# nRF24L01_RFX2401_noBalun_SMD_0603.net
KiCad netlist of a schematic drawn in EAGLE
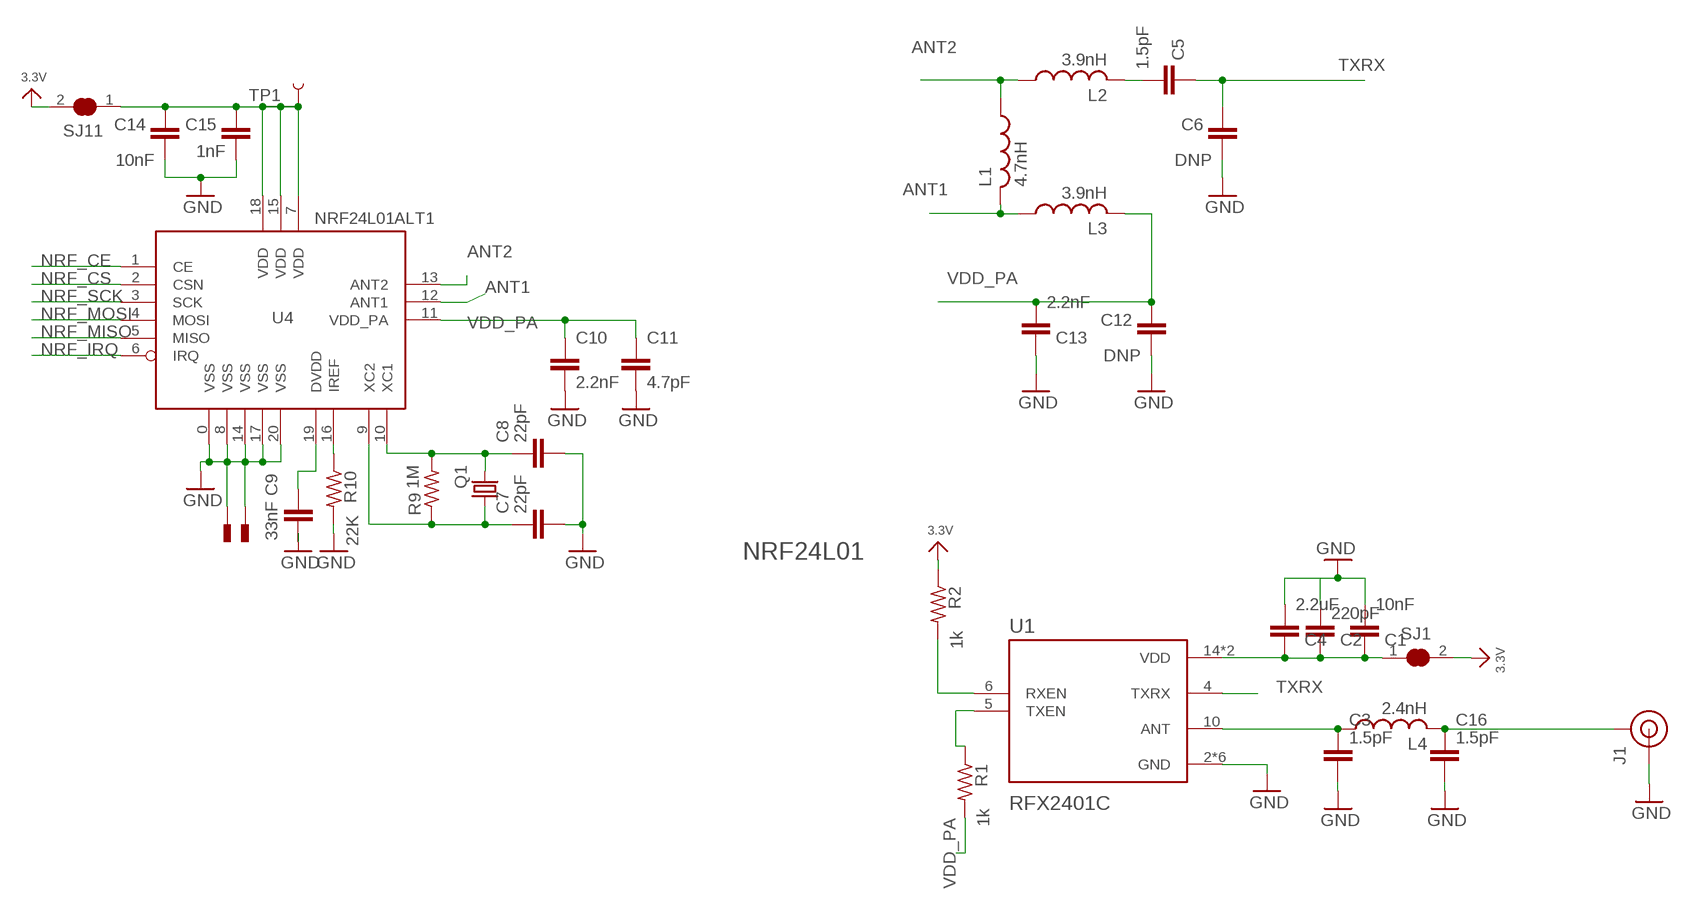
[diagram p0: schematic, sheet 1]

(export (version "E")
  (design (tool "Eeschema 10.0.6"))
  (components
    (comp (ref "C1")
      (value "10nF")
      (footprint "eagle-import:C0603")
      (libsource (lib "eagle-import") (part "C-EUC0603"))
    )
    (comp (ref "C2")
      (value "220pF")
      (footprint "eagle-import:C0603")
      (libsource (lib "eagle-import") (part "C-EUC0603"))
    )
    (comp (ref "C3")
      (value "1.5pF")
      (footprint "eagle-import:C0603")
      (libsource (lib "eagle-import") (part "C-EUC0603"))
    )
    (comp (ref "C4")
      (value "2.2uF")
      (footprint "eagle-import:C0603")
      (libsource (lib "eagle-import") (part "C-EUC0603"))
    )
    (comp (ref "C5")
      (value "1.5pF")
      (footprint "eagle-import:C0603")
      (libsource (lib "eagle-import") (part "C-EUC0603"))
    )
    (comp (ref "C6")
      (value "DNP")
      (footprint "eagle-import:C0603")
      (libsource (lib "eagle-import") (part "C-EUC0603"))
    )
    (comp (ref "C7")
      (value "22pF")
      (footprint "eagle-import:C0603")
      (libsource (lib "eagle-import") (part "C-EUC0603"))
    )
    (comp (ref "C8")
      (value "22pF")
      (footprint "eagle-import:C0603")
      (libsource (lib "eagle-import") (part "C-EUC0603"))
    )
    (comp (ref "C9")
      (value "33nF")
      (footprint "eagle-import:C0603")
      (libsource (lib "eagle-import") (part "C-EUC0603"))
    )
    (comp (ref "C10")
      (value "2.2nF")
      (footprint "eagle-import:C0603")
      (libsource (lib "eagle-import") (part "C-EUC0603"))
    )
    (comp (ref "C11")
      (value "4.7pF")
      (footprint "eagle-import:C0603")
      (libsource (lib "eagle-import") (part "C-EUC0603"))
    )
    (comp (ref "C12")
      (value "DNP")
      (footprint "eagle-import:C0603")
      (libsource (lib "eagle-import") (part "C-EUC0603"))
    )
    (comp (ref "C13")
      (value "2.2nF")
      (footprint "eagle-import:C0603")
      (libsource (lib "eagle-import") (part "C-EUC0603"))
    )
    (comp (ref "C14")
      (value "10nF")
      (footprint "eagle-import:C0603")
      (libsource (lib "eagle-import") (part "C-EUC0603"))
    )
    (comp (ref "C15")
      (value "1nF")
      (footprint "eagle-import:C0603")
      (libsource (lib "eagle-import") (part "C-EUC0603"))
    )
    (comp (ref "C16")
      (value "1.5pF")
      (footprint "eagle-import:C0603")
      (libsource (lib "eagle-import") (part "C-EUC0603"))
    )
    (comp (ref "J1")
      (value "U.FL")
      (footprint "eagle-import:U.FL")
      (libsource (lib "eagle-import") (part "U.FL2PIN"))
    )
    (comp (ref "L1")
      (value "4.7nH")
      (footprint "eagle-import:L0603")
      (libsource (lib "eagle-import") (part "L-USL0603"))
    )
    (comp (ref "L2")
      (value "3.9nH")
      (footprint "eagle-import:L0603")
      (libsource (lib "eagle-import") (part "L-USL0603"))
    )
    (comp (ref "L3")
      (value "3.9nH")
      (footprint "eagle-import:L0603")
      (libsource (lib "eagle-import") (part "L-USL0603"))
    )
    (comp (ref "L4")
      (value "2.4nH")
      (footprint "eagle-import:L0603")
      (libsource (lib "eagle-import") (part "L-USL0603"))
    )
    (comp (ref "Q1")
      (value "KX-7")
      (footprint "eagle-import:3.2X2.5_KX-7")
      (libsource (lib "eagle-import") (part "KX-7"))
    )
    (comp (ref "R1")
      (value "1k")
      (footprint "eagle-import:R0603")
      (libsource (lib "eagle-import") (part "R-US_R0603"))
    )
    (comp (ref "R2")
      (value "1k")
      (footprint "eagle-import:R0603")
      (libsource (lib "eagle-import") (part "R-US_R0603"))
    )
    (comp (ref "R9")
      (value "1M")
      (footprint "eagle-import:R0603")
      (libsource (lib "eagle-import") (part "R-US_R0603"))
    )
    (comp (ref "R10")
      (value "22K")
      (footprint "eagle-import:R0603")
      (libsource (lib "eagle-import") (part "R-US_R0603"))
    )
    (comp (ref "SJ1")
      (value "SOLDERJUMPER_CLOSED")
      (footprint "eagle-import:SOLDERJUMPER_CLOSEDWIRE")
      (libsource (lib "eagle-import") (part "SOLDERJUMPER_CLOSED"))
    )
    (comp (ref "SJ11")
      (value "SOLDERJUMPER_CLOSED")
      (footprint "eagle-import:SOLDERJUMPER_CLOSEDWIRE")
      (libsource (lib "eagle-import") (part "SOLDERJUMPER_CLOSED"))
    )
    (comp (ref "TP1")
      (value "TEST-POINT3X5")
      (footprint "eagle-import:PAD.03X.05")
      (libsource (lib "eagle-import") (part "TEST-POINT3X5"))
    )
    (comp (ref "U$27")
      (value "PAD")
      (footprint "eagle-import:PAD-0.008")
      (libsource (lib "eagle-import") (part "PAD"))
    )
    (comp (ref "U$28")
      (value "PAD")
      (footprint "eagle-import:PAD-0.008")
      (libsource (lib "eagle-import") (part "PAD"))
    )
    (comp (ref "U1")
      (value "RFX2401C")
      (footprint "eagle-import:QFN50P300X300X60-17N")
      (fields (field (name "MF") "Skyworks Solutions"))
      (libsource (lib "eagle-import") (part "RFX2401C"))
    )
    (comp (ref "U4")
      (value "NRF24L01ALT1")
      (footprint "eagle-import:QFN20_ALT1")
      (libsource (lib "eagle-import") (part "NRF24L01ALT1"))
    )
  )
  (nets
    (net (code "1") (name "/ANT1") (class "Default")
      (node (ref "L1") (pin "2") (pinfunction "2_2") (pintype "passive"))
      (node (ref "L3") (pin "1") (pinfunction "1_1") (pintype "passive"))
      (node (ref "U4") (pin "12") (pinfunction "ANT1_12") (pintype "output"))
    )
    (net (code "2") (name "/ANT2") (class "Default")
      (node (ref "L1") (pin "1") (pinfunction "1_1") (pintype "passive"))
      (node (ref "L2") (pin "1") (pinfunction "1_1") (pintype "passive"))
      (node (ref "U4") (pin "13") (pinfunction "ANT2_13") (pintype "output"))
    )
    (net (code "3") (name "/NRF_CE") (class "Default")
      (node (ref "U4") (pin "1") (pinfunction "CE_1") (pintype "input"))
    )
    (net (code "4") (name "/NRF_CS") (class "Default")
      (node (ref "U4") (pin "2") (pinfunction "CSN_2") (pintype "input"))
    )
    (net (code "5") (name "/NRF_IRQ") (class "Default")
      (node (ref "U4") (pin "6") (pinfunction "IRQ_6") (pintype "output"))
    )
    (net (code "6") (name "/NRF_MISO") (class "Default")
      (node (ref "U4") (pin "5") (pinfunction "MISO_5") (pintype "output"))
    )
    (net (code "7") (name "/NRF_MOSI") (class "Default")
      (node (ref "U4") (pin "4") (pinfunction "MOSI_4") (pintype "input"))
    )
    (net (code "8") (name "/NRF_SCK") (class "Default")
      (node (ref "U4") (pin "3") (pinfunction "SCK_3") (pintype "input"))
    )
    (net (code "9") (name "/TXRX") (class "Default")
      (node (ref "C5") (pin "2") (pinfunction "2_2") (pintype "passive"))
      (node (ref "C6") (pin "2") (pinfunction "2_2") (pintype "passive"))
      (node (ref "U1") (pin "4") (pinfunction "TXRX_4") (pintype "bidirectional"))
    )
    (net (code "10") (name "/VDD_PA") (class "Default")
      (node (ref "C10") (pin "1") (pinfunction "1_1") (pintype "passive"))
      (node (ref "C11") (pin "1") (pinfunction "1_1") (pintype "passive"))
      (node (ref "C12") (pin "2") (pinfunction "2_2") (pintype "passive"))
      (node (ref "C13") (pin "1") (pinfunction "1_1") (pintype "passive"))
      (node (ref "L3") (pin "2") (pinfunction "2_2") (pintype "passive"))
      (node (ref "R1") (pin "2") (pinfunction "2_2") (pintype "passive"))
      (node (ref "U4") (pin "11") (pinfunction "VDD_PA_11") (pintype "power_in"))
    )
    (net (code "11") (name "3.3V") (class "Default")
      (node (ref "R2") (pin "1") (pinfunction "1_1") (pintype "passive"))
      (node (ref "SJ1") (pin "2") (pinfunction "2_2") (pintype "passive"))
      (node (ref "SJ11") (pin "2") (pinfunction "2_2") (pintype "passive"))
    )
    (net (code "12") (name "GND") (class "Default")
      (node (ref "C1") (pin "1") (pinfunction "1_1") (pintype "passive"))
      (node (ref "C10") (pin "2") (pinfunction "2_2") (pintype "passive"))
      (node (ref "C11") (pin "2") (pinfunction "2_2") (pintype "passive"))
      (node (ref "C12") (pin "1") (pinfunction "1_1") (pintype "passive"))
      (node (ref "C13") (pin "2") (pinfunction "2_2") (pintype "passive"))
      (node (ref "C14") (pin "1") (pinfunction "1_1") (pintype "passive"))
      (node (ref "C15") (pin "1") (pinfunction "1_1") (pintype "passive"))
      (node (ref "C16") (pin "2") (pinfunction "2_2") (pintype "passive"))
      (node (ref "C2") (pin "1") (pinfunction "1_1") (pintype "passive"))
      (node (ref "C3") (pin "2") (pinfunction "2_2") (pintype "passive"))
      (node (ref "C4") (pin "1") (pinfunction "1_1") (pintype "passive"))
      (node (ref "C6") (pin "1") (pinfunction "1_1") (pintype "passive"))
      (node (ref "C7") (pin "2") (pinfunction "2_2") (pintype "passive"))
      (node (ref "C8") (pin "2") (pinfunction "2_2") (pintype "passive"))
      (node (ref "C9") (pin "2") (pinfunction "2_2") (pintype "passive"))
      (node (ref "J1") (pin "FEED") (pinfunction "SIGNAL_FEED") (pintype "bidirectional"))
      (node (ref "R10") (pin "2") (pinfunction "2_2") (pintype "passive"))
      (node (ref "U$27") (pin "P$1") (pinfunction "P$1_P$1") (pintype "bidirectional"))
      (node (ref "U$28") (pin "P$1") (pinfunction "P$1_P$1") (pintype "bidirectional"))
      (node (ref "U1") (pin "11") (pinfunction "GND_11") (pintype "power_in"))
      (node (ref "U1") (pin "17") (pinfunction "GND_17") (pintype "power_in"))
      (node (ref "U1") (pin "2") (pinfunction "GND_2") (pintype "power_in"))
      (node (ref "U1") (pin "3") (pinfunction "GND_3") (pintype "power_in"))
      (node (ref "U1") (pin "8") (pinfunction "GND_8") (pintype "power_in"))
      (node (ref "U1") (pin "9") (pinfunction "GND_9") (pintype "power_in"))
      (node (ref "U4") (pin "0") (pinfunction "VSS_0") (pintype "power_in"))
      (node (ref "U4") (pin "14") (pinfunction "VSS_14") (pintype "power_in"))
      (node (ref "U4") (pin "17") (pinfunction "VSS_17") (pintype "power_in"))
      (node (ref "U4") (pin "20") (pinfunction "VSS_20") (pintype "power_in"))
      (node (ref "U4") (pin "8") (pinfunction "VSS_8") (pintype "power_in"))
    )
    (net (code "13") (name "Net-(C1-Pad2)") (class "Default")
      (node (ref "C1") (pin "2") (pinfunction "2_2") (pintype "passive"))
      (node (ref "C2") (pin "2") (pinfunction "2_2") (pintype "passive"))
      (node (ref "C4") (pin "2") (pinfunction "2_2") (pintype "passive"))
      (node (ref "SJ1") (pin "1") (pinfunction "1_1") (pintype "passive"))
      (node (ref "U1") (pin "14") (pinfunction "VDD_14") (pintype "power_in"))
      (node (ref "U1") (pin "16") (pinfunction "VDD_16") (pintype "power_in"))
    )
    (net (code "14") (name "Net-(C5-Pad1)") (class "Default")
      (node (ref "C5") (pin "1") (pinfunction "1_1") (pintype "passive"))
      (node (ref "L2") (pin "2") (pinfunction "2_2") (pintype "passive"))
    )
    (net (code "15") (name "Net-(C16-Pad1)") (class "Default")
      (node (ref "C16") (pin "1") (pinfunction "1_1") (pintype "passive"))
      (node (ref "J1") (pin "1") (pinfunction "GND_1") (pintype "bidirectional"))
      (node (ref "J1") (pin "2") (pinfunction "GND_2") (pintype "bidirectional"))
      (node (ref "L4") (pin "2") (pinfunction "2_2") (pintype "passive"))
    )
    (net (code "16") (name "Net-(Q1-2)") (class "Default")
      (node (ref "C8") (pin "1") (pinfunction "1_1") (pintype "passive"))
      (node (ref "Q1") (pin "3") (pinfunction "2_3") (pintype "passive"))
      (node (ref "R9") (pin "2") (pinfunction "2_2") (pintype "passive"))
      (node (ref "U4") (pin "10") (pinfunction "XC1_10") (pintype "input"))
    )
    (net (code "17") (name "Net-(TP1-1)") (class "Default")
      (node (ref "C14") (pin "2") (pinfunction "2_2") (pintype "passive"))
      (node (ref "C15") (pin "2") (pinfunction "2_2") (pintype "passive"))
      (node (ref "SJ11") (pin "1") (pinfunction "1_1") (pintype "passive"))
      (node (ref "TP1") (pin "P$1") (pinfunction "1_P$1") (pintype "bidirectional"))
      (node (ref "U4") (pin "15") (pinfunction "VDD_15") (pintype "power_in"))
      (node (ref "U4") (pin "18") (pinfunction "VDD_18") (pintype "power_in"))
      (node (ref "U4") (pin "7") (pinfunction "VDD_7") (pintype "power_in"))
    )
    (net (code "18") (name "Net-(U1-ANT)") (class "Default")
      (node (ref "C3") (pin "1") (pinfunction "1_1") (pintype "passive"))
      (node (ref "L4") (pin "1") (pinfunction "1_1") (pintype "passive"))
      (node (ref "U1") (pin "10") (pinfunction "ANT_10") (pintype "passive"))
    )
    (net (code "19") (name "Net-(U1-RXEN)") (class "Default")
      (node (ref "R2") (pin "2") (pinfunction "2_2") (pintype "passive"))
      (node (ref "U1") (pin "6") (pinfunction "RXEN_6") (pintype "input"))
    )
    (net (code "20") (name "Net-(U1-TXEN)") (class "Default")
      (node (ref "R1") (pin "1") (pinfunction "1_1") (pintype "passive"))
      (node (ref "U1") (pin "5") (pinfunction "TXEN_5") (pintype "input"))
    )
    (net (code "21") (name "Net-(U4-DVDD)") (class "Default")
      (node (ref "C9") (pin "1") (pinfunction "1_1") (pintype "passive"))
      (node (ref "U4") (pin "19") (pinfunction "DVDD_19") (pintype "power_in"))
    )
    (net (code "22") (name "Net-(U4-IREF)") (class "Default")
      (node (ref "R10") (pin "1") (pinfunction "1_1") (pintype "passive"))
      (node (ref "U4") (pin "16") (pinfunction "IREF_16") (pintype "input"))
    )
    (net (code "23") (name "Net-(U4-XC2)") (class "Default")
      (node (ref "C7") (pin "1") (pinfunction "1_1") (pintype "passive"))
      (node (ref "Q1") (pin "1") (pinfunction "1_1") (pintype "passive"))
      (node (ref "R9") (pin "1") (pinfunction "1_1") (pintype "passive"))
      (node (ref "U4") (pin "9") (pinfunction "XC2_9") (pintype "input"))
    )
  )
)
